# 06.net
KiCad netlist of a schematic drawn in Altium Designer
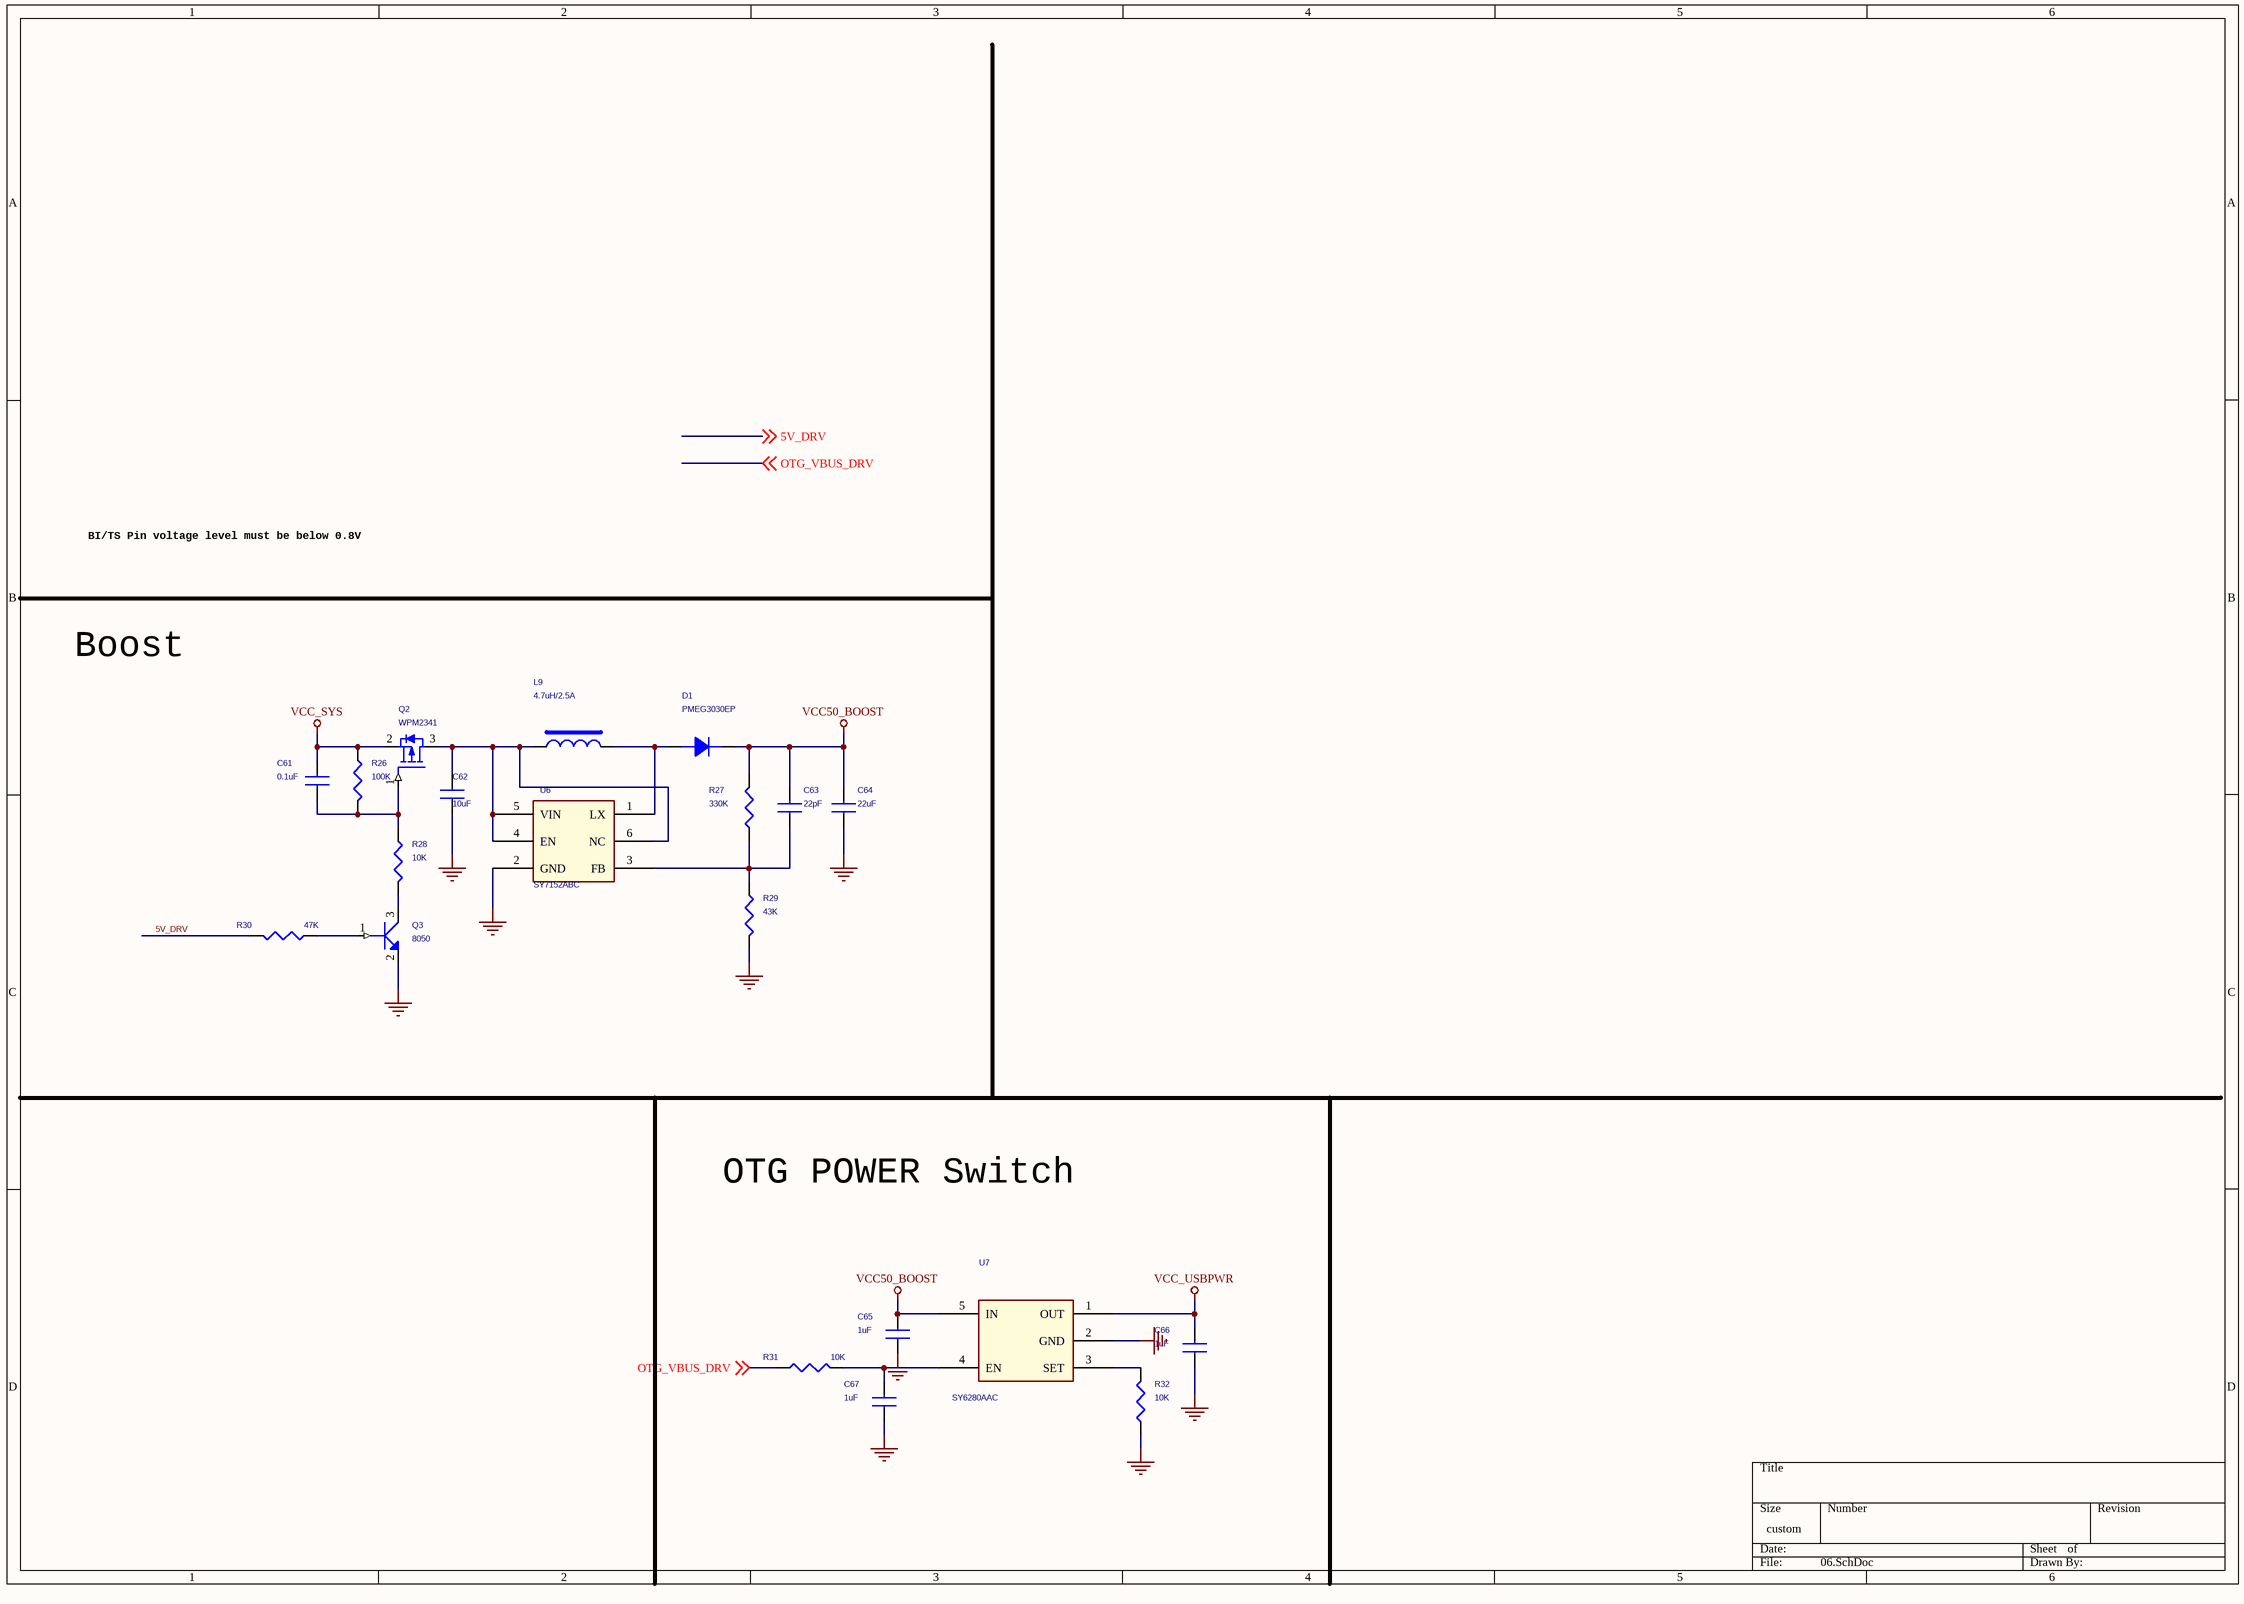
[diagram p0: 06.SchDoc]

(export (version "E")
  (design (tool "Eeschema 10.0.6"))
  (components
    (comp (ref "C61")
      (value "0.1uF")
      (footprint "C0603")
      (description "RoHS CHIP CAP 0.1uF +10/-10% X7R")
      (libsource (lib "*") (part "CAP NP_Dup3"))
    )
    (comp (ref "C62")
      (value "10uF")
      (footprint "C0603")
      (description "RoHS CHIP CAP 10uF +10/-10% X5R")
      (libsource (lib "*") (part "CAP NP_Dup3"))
    )
    (comp (ref "C63")
      (value "22pF")
      (footprint "C0603")
      (description "RoHS CHIP CAP 22pF 1% NPO")
      (libsource (lib "*") (part "CAP NP_Dup3"))
    )
    (comp (ref "C64")
      (value "22uF")
      (footprint "C0603")
      (description "RoHS CHIP CAP 10uF +10/-10% X5R")
      (libsource (lib "*") (part "CAP NP_Dup3"))
    )
    (comp (ref "C65")
      (value "1uF")
      (footprint "C0603")
      (description "RoHS CHIP CAP 0.1uF +10/-10% X7R")
      (libsource (lib "*") (part "CAP NP_Dup3"))
    )
    (comp (ref "C66")
      (value "1uF")
      (footprint "C0603")
      (description "RoHS CHIP CAP 0.1uF +10/-10% X7R")
      (libsource (lib "*") (part "CAP NP_Dup3"))
    )
    (comp (ref "C67")
      (value "1uF")
      (footprint "C0603")
      (description "RoHS CHIP CAP 0.1uF +10/-10% X7R")
      (libsource (lib "*") (part "CAP NP_Dup3"))
    )
    (comp (ref "D1")
      (value "PMEG3030EP")
      (footprint "DO214AC")
      (description "RoHS 1.0A SURFACE MOUNT SCHOTTKY BARRIER RECTIFIER 1N5819")
      (libsource (lib "*") (part "DIODE_Dup2"))
    )
    (comp (ref "L9")
      (value "4.7uH/2.5A")
      (footprint "IND-3X3")
      (description "CoilInd,Shielded(SHLD),4.7uH@100KHz,+/-30%,1.5A,45mOhm,SMD,4.0*4.0*2.0")
      (libsource (lib "*") (part "INDUCTOR_1"))
    )
    (comp (ref "Q2")
      (value "WPM2341")
      (footprint "SOT23")
      (description "MOSFET-P,WPM2341 ,-20V,+/-8V,-2.8A,56m Ohm@Vgs=-2.5V,44m Ohm@Vgs=-4.5V,SOT23")
      (libsource (lib "*") (part "MOSFET P"))
    )
    (comp (ref "Q3") (value "8050") (footprint "SOT23") (libsource (lib "*") (part "NPN4")))
    (comp (ref "R26")
      (value "100K")
      (footprint "r0402")
      (description "ROHS CHIP RES 100K 1/16W 1%")
      (libsource (lib "*") (part "RES 1B_Dup1"))
    )
    (comp (ref "R27")
      (value "330K")
      (footprint "r0402")
      (description "ROHS CHIP RES 330K 1/16W +/-5%")
      (libsource (lib "*") (part "RESISTOR_0_Dup2"))
    )
    (comp (ref "R28")
      (value "10K")
      (footprint "r0402")
      (description "RES,thick film,47KOhm,+/-5%,1/16W,SMD0402")
      (libsource (lib "*") (part "RESISTOR_1_Dup2"))
    )
    (comp (ref "R29")
      (value "43K")
      (footprint "r0402")
      (description "ROHS CHIP RES 43K 1/16W +/-5%")
      (libsource (lib "*") (part "RESISTOR_0_Dup2"))
    )
    (comp (ref "R30")
      (value "47K")
      (footprint "r0402")
      (description "RES,thick film,47KOhm,+/-5%,1/16W,SMD0402")
      (libsource (lib "*") (part "RESISTOR_1_Dup2"))
    )
    (comp (ref "R31")
      (value "10K")
      (footprint "R0402")
      (description "ROHS CHIP RES 4.7K 1/16W +/-5%")
      (libsource (lib "*") (part "RESISTOR_Dup1"))
    )
    (comp (ref "R32")
      (value "10K")
      (footprint "R0402")
      (description "ROHS CHIP RES 10K 1/16W +/-5%")
      (libsource (lib "*") (part "RESISTOR_Dup1"))
    )
    (comp (ref "U6")
      (value "SY7152ABC")
      (footprint "SOT26")
      (description "SY7208/TCS9208/LP6218 High Efficiency 1MHz, 2A Step Up Regulator")
      (libsource (lib "*") (part "G5121_1"))
    )
    (comp (ref "U7")
      (value "SY6280AAC")
      (footprint "SOT25")
      (description "Power switch,LPW5206H,2.4V~5.5V,SOT23-5,-40°C~+ 85°C")
      (libsource (lib "*") (part "LPW5206H"))
    )
  )
  (nets
    (net (code "1") (name "5V_DRV") (class "Default")
      (node (ref "R30") (pin "1") (pinfunction "1_1") (pintype "passive"))
    )
    (net (code "2") (name "GND") (class "Default")
      (node (ref "C62") (pin "1") (pinfunction "1_1") (pintype "passive"))
      (node (ref "C64") (pin "1") (pinfunction "1_1") (pintype "passive"))
      (node (ref "C65") (pin "1") (pinfunction "1_1") (pintype "passive"))
      (node (ref "C66") (pin "1") (pinfunction "1_1") (pintype "passive"))
      (node (ref "C67") (pin "1") (pinfunction "1_1") (pintype "passive"))
      (node (ref "Q3") (pin "2") (pinfunction "E_2") (pintype "passive"))
      (node (ref "R29") (pin "2") (pinfunction "2_2") (pintype "passive"))
      (node (ref "R32") (pin "1") (pinfunction "1_1") (pintype "passive"))
      (node (ref "U6") (pin "2") (pinfunction "GND_2") (pintype "passive"))
      (node (ref "U7") (pin "2") (pinfunction "GND_2") (pintype "passive"))
    )
    (net (code "3") (name "Net-(D1-A)") (class "Default")
      (node (ref "D1") (pin "1") (pinfunction "A_1") (pintype "passive"))
      (node (ref "L9") (pin "2") (pinfunction "2_2") (pintype "passive"))
      (node (ref "U6") (pin "1") (pinfunction "LX_1") (pintype "passive"))
    )
    (net (code "4") (name "Net-(Q2-DRAIN)") (class "Default")
      (node (ref "C62") (pin "2") (pinfunction "2_2") (pintype "passive"))
      (node (ref "L9") (pin "1") (pinfunction "1_1") (pintype "passive"))
      (node (ref "Q2") (pin "3") (pinfunction "DRAIN_3") (pintype "passive"))
      (node (ref "U6") (pin "4") (pinfunction "EN_4") (pintype "passive"))
      (node (ref "U6") (pin "5") (pinfunction "VIN_5") (pintype "passive"))
      (node (ref "U6") (pin "6") (pinfunction "NC_6") (pintype "passive"))
    )
    (net (code "5") (name "Net-(Q2-GATE)") (class "Default")
      (node (ref "C61") (pin "1") (pinfunction "1_1") (pintype "passive"))
      (node (ref "Q2") (pin "1") (pinfunction "GATE_1") (pintype "input"))
      (node (ref "R26") (pin "1") (pinfunction "1_1") (pintype "passive"))
      (node (ref "R28") (pin "2") (pinfunction "2_2") (pintype "passive"))
    )
    (net (code "6") (name "Net-(Q3-B)") (class "Default")
      (node (ref "Q3") (pin "1") (pinfunction "B_1") (pintype "input"))
      (node (ref "R30") (pin "2") (pinfunction "2_2") (pintype "passive"))
    )
    (net (code "7") (name "Net-(Q3-C)") (class "Default")
      (node (ref "Q3") (pin "3") (pinfunction "C_3") (pintype "passive"))
      (node (ref "R28") (pin "1") (pinfunction "1_1") (pintype "passive"))
    )
    (net (code "8") (name "Net-(U6-FB)") (class "Default")
      (node (ref "C63") (pin "1") (pinfunction "1_1") (pintype "passive"))
      (node (ref "R27") (pin "2") (pinfunction "2_2") (pintype "passive"))
      (node (ref "R29") (pin "1") (pinfunction "1_1") (pintype "passive"))
      (node (ref "U6") (pin "3") (pinfunction "FB_3") (pintype "passive"))
    )
    (net (code "9") (name "Net-(U7-EN)") (class "Default")
      (node (ref "C67") (pin "2") (pinfunction "2_2") (pintype "passive"))
      (node (ref "R31") (pin "1") (pinfunction "1_1") (pintype "passive"))
      (node (ref "U7") (pin "4") (pinfunction "EN_4") (pintype "passive"))
    )
    (net (code "10") (name "Net-(U7-SET)") (class "Default")
      (node (ref "R32") (pin "2") (pinfunction "2_2") (pintype "passive"))
      (node (ref "U7") (pin "3") (pinfunction "SET_3") (pintype "passive"))
    )
    (net (code "11") (name "OTG_VBUS_DRV") (class "Default")
      (node (ref "R31") (pin "2") (pinfunction "2_2") (pintype "passive"))
    )
    (net (code "12") (name "VCC50_BOOST") (class "Default")
      (node (ref "C63") (pin "2") (pinfunction "2_2") (pintype "passive"))
      (node (ref "C64") (pin "2") (pinfunction "2_2") (pintype "passive"))
      (node (ref "C65") (pin "2") (pinfunction "2_2") (pintype "passive"))
      (node (ref "D1") (pin "2") (pinfunction "K_2") (pintype "passive"))
      (node (ref "R27") (pin "1") (pinfunction "1_1") (pintype "passive"))
      (node (ref "U7") (pin "5") (pinfunction "IN_5") (pintype "passive"))
    )
    (net (code "13") (name "VCC_SYS") (class "Default")
      (node (ref "C61") (pin "2") (pinfunction "2_2") (pintype "passive"))
      (node (ref "Q2") (pin "2") (pinfunction "SOURCE_2") (pintype "passive"))
      (node (ref "R26") (pin "2") (pinfunction "2_2") (pintype "passive"))
    )
    (net (code "14") (name "VCC_USBPWR") (class "Default")
      (node (ref "C66") (pin "2") (pinfunction "2_2") (pintype "passive"))
      (node (ref "U7") (pin "1") (pinfunction "OUT_1") (pintype "passive"))
    )
  )
)
